# 3DO.net
KiCad netlist of a schematic drawn in EAGLE
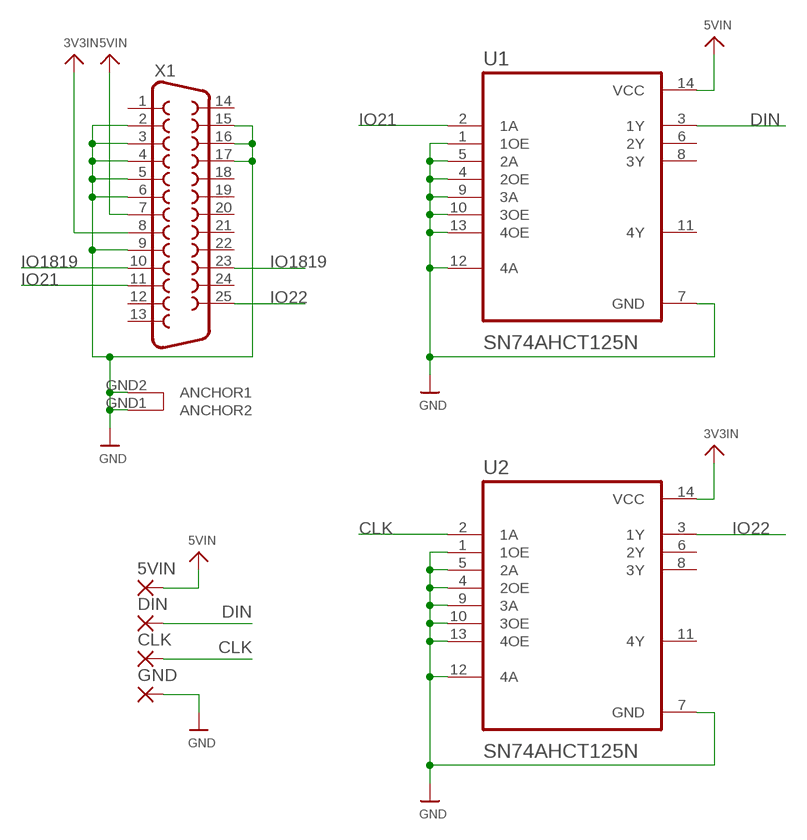
[diagram p0: schematic, sheet 1]

(export (version "E")
  (design (tool "Eeschema 10.0.6"))
  (components
    (comp (ref "5VIN")
      (value "SMD5")
      (footprint "eagle-import:SMD2,54-5,08")
      (libsource (lib "eagle-import") (part "SMD5"))
    )
    (comp (ref "CLK")
      (value "SMD5")
      (footprint "eagle-import:SMD2,54-5,08")
      (libsource (lib "eagle-import") (part "SMD5"))
    )
    (comp (ref "DIN")
      (value "SMD5")
      (footprint "eagle-import:SMD2,54-5,08")
      (libsource (lib "eagle-import") (part "SMD5"))
    )
    (comp (ref "GND")
      (value "SMD5")
      (footprint "eagle-import:SMD2,54-5,08")
      (libsource (lib "eagle-import") (part "SMD5"))
    )
    (comp (ref "U1")
      (value "SN74AHCT125N")
      (footprint "eagle-import:DIP794W45P254L1969H508Q14")
      (fields (field (name "MF") "Texas Instruments"))
      (libsource (lib "eagle-import") (part "SN74AHCT125N"))
    )
    (comp (ref "U2")
      (value "SN74AHCT125N")
      (footprint "eagle-import:DIP794W45P254L1969H508Q14")
      (fields (field (name "MF") "Texas Instruments"))
      (libsource (lib "eagle-import") (part "SN74AHCT125N"))
    )
    (comp (ref "X1")
      (value "DB25_FEMALEHP")
      (footprint "eagle-import:F25HP")
      (libsource (lib "eagle-import") (part "DB25_FEMALEHP"))
    )
  )
  (nets
    (net (code "1") (name "/CLK") (class "Default")
      (node (ref "CLK") (pin "1") (pinfunction "P_1") (pintype "passive"))
      (node (ref "U2") (pin "2") (pinfunction "1A_2") (pintype "input"))
    )
    (net (code "2") (name "/DIN") (class "Default")
      (node (ref "DIN") (pin "1") (pinfunction "P_1") (pintype "passive"))
      (node (ref "U1") (pin "3") (pinfunction "1Y_3") (pintype "output"))
    )
    (net (code "3") (name "/IO21") (class "Default")
      (node (ref "U1") (pin "2") (pinfunction "1A_2") (pintype "input"))
      (node (ref "X1") (pin "11") (pinfunction "11_11") (pintype "passive"))
    )
    (net (code "4") (name "/IO22") (class "Default")
      (node (ref "U2") (pin "3") (pinfunction "1Y_3") (pintype "output"))
      (node (ref "X1") (pin "25") (pinfunction "25_25") (pintype "passive"))
    )
    (net (code "5") (name "/IO1819") (class "Default")
      (node (ref "X1") (pin "10") (pinfunction "10_10") (pintype "passive"))
      (node (ref "X1") (pin "23") (pinfunction "23_23") (pintype "passive"))
    )
    (net (code "6") (name "3V3IN") (class "Default")
      (node (ref "U2") (pin "14") (pinfunction "VCC_14") (pintype "power_in"))
      (node (ref "X1") (pin "8") (pinfunction "8_8") (pintype "passive"))
    )
    (net (code "7") (name "5VIN") (class "Default")
      (node (ref "5VIN") (pin "1") (pinfunction "P_1") (pintype "passive"))
      (node (ref "U1") (pin "14") (pinfunction "VCC_14") (pintype "power_in"))
      (node (ref "X1") (pin "7") (pinfunction "7_7") (pintype "passive"))
    )
    (net (code "8") (name "GND") (class "Default")
      (node (ref "GND") (pin "1") (pinfunction "P_1") (pintype "passive"))
      (node (ref "U1") (pin "1") (pinfunction "1OE_1") (pintype "input"))
      (node (ref "U1") (pin "10") (pinfunction "3OE_10") (pintype "input"))
      (node (ref "U1") (pin "12") (pinfunction "4A_12") (pintype "bidirectional"))
      (node (ref "U1") (pin "13") (pinfunction "4OE_13") (pintype "input"))
      (node (ref "U1") (pin "4") (pinfunction "2OE_4") (pintype "input"))
      (node (ref "U1") (pin "5") (pinfunction "2A_5") (pintype "input"))
      (node (ref "U1") (pin "7") (pinfunction "GND_7") (pintype "power_in"))
      (node (ref "U1") (pin "9") (pinfunction "3A_9") (pintype "input"))
      (node (ref "U2") (pin "1") (pinfunction "1OE_1") (pintype "input"))
      (node (ref "U2") (pin "10") (pinfunction "3OE_10") (pintype "input"))
      (node (ref "U2") (pin "12") (pinfunction "4A_12") (pintype "bidirectional"))
      (node (ref "U2") (pin "13") (pinfunction "4OE_13") (pintype "input"))
      (node (ref "U2") (pin "4") (pinfunction "2OE_4") (pintype "input"))
      (node (ref "U2") (pin "5") (pinfunction "2A_5") (pintype "input"))
      (node (ref "U2") (pin "7") (pinfunction "GND_7") (pintype "power_in"))
      (node (ref "U2") (pin "9") (pinfunction "3A_9") (pintype "input"))
      (node (ref "X1") (pin "15") (pinfunction "15_15") (pintype "passive"))
      (node (ref "X1") (pin "16") (pinfunction "16_16") (pintype "passive"))
      (node (ref "X1") (pin "17") (pinfunction "17_17") (pintype "passive"))
      (node (ref "X1") (pin "2") (pinfunction "2_2") (pintype "passive"))
      (node (ref "X1") (pin "3") (pinfunction "3_3") (pintype "passive"))
      (node (ref "X1") (pin "4") (pinfunction "4_4") (pintype "passive"))
      (node (ref "X1") (pin "5") (pinfunction "5_5") (pintype "passive"))
      (node (ref "X1") (pin "6") (pinfunction "6_6") (pintype "passive"))
      (node (ref "X1") (pin "9") (pinfunction "9_9") (pintype "passive"))
      (node (ref "X1") (pin "GND1") (pinfunction "ANCHOR2_GND1") (pintype "bidirectional"))
      (node (ref "X1") (pin "GND2") (pinfunction "ANCHOR1_GND2") (pintype "bidirectional"))
    )
    (net (code "9") (name "unconnected-(U1-2Y-Pad6)") (class "Default")
      (node (ref "U1") (pin "6") (pinfunction "2Y_6") (pintype "output"))
    )
    (net (code "10") (name "unconnected-(U1-3Y-Pad8)") (class "Default")
      (node (ref "U1") (pin "8") (pinfunction "3Y_8") (pintype "output"))
    )
    (net (code "11") (name "unconnected-(U1-4Y-Pad11)") (class "Default")
      (node (ref "U1") (pin "11") (pinfunction "4Y_11") (pintype "output"))
    )
    (net (code "12") (name "unconnected-(U2-2Y-Pad6)") (class "Default")
      (node (ref "U2") (pin "6") (pinfunction "2Y_6") (pintype "output"))
    )
    (net (code "13") (name "unconnected-(U2-3Y-Pad8)") (class "Default")
      (node (ref "U2") (pin "8") (pinfunction "3Y_8") (pintype "output"))
    )
    (net (code "14") (name "unconnected-(U2-4Y-Pad11)") (class "Default")
      (node (ref "U2") (pin "11") (pinfunction "4Y_11") (pintype "output"))
    )
    (net (code "15") (name "unconnected-(X1-Pad1)") (class "Default")
      (node (ref "X1") (pin "1") (pinfunction "1_1") (pintype "passive"))
    )
    (net (code "16") (name "unconnected-(X1-Pad12)") (class "Default")
      (node (ref "X1") (pin "12") (pinfunction "12_12") (pintype "passive"))
    )
    (net (code "17") (name "unconnected-(X1-Pad13)") (class "Default")
      (node (ref "X1") (pin "13") (pinfunction "13_13") (pintype "passive"))
    )
    (net (code "18") (name "unconnected-(X1-Pad14)") (class "Default")
      (node (ref "X1") (pin "14") (pinfunction "14_14") (pintype "passive"))
    )
    (net (code "19") (name "unconnected-(X1-Pad18)") (class "Default")
      (node (ref "X1") (pin "18") (pinfunction "18_18") (pintype "passive"))
    )
    (net (code "20") (name "unconnected-(X1-Pad19)") (class "Default")
      (node (ref "X1") (pin "19") (pinfunction "19_19") (pintype "passive"))
    )
    (net (code "21") (name "unconnected-(X1-Pad20)") (class "Default")
      (node (ref "X1") (pin "20") (pinfunction "20_20") (pintype "passive"))
    )
    (net (code "22") (name "unconnected-(X1-Pad21)") (class "Default")
      (node (ref "X1") (pin "21") (pinfunction "21_21") (pintype "passive"))
    )
    (net (code "23") (name "unconnected-(X1-Pad22)") (class "Default")
      (node (ref "X1") (pin "22") (pinfunction "22_22") (pintype "passive"))
    )
    (net (code "24") (name "unconnected-(X1-Pad24)") (class "Default")
      (node (ref "X1") (pin "24") (pinfunction "24_24") (pintype "passive"))
    )
  )
)
